# SCH_HackerCard_2024-08-30.net
KiCad netlist of a schematic drawn in EasyEDA
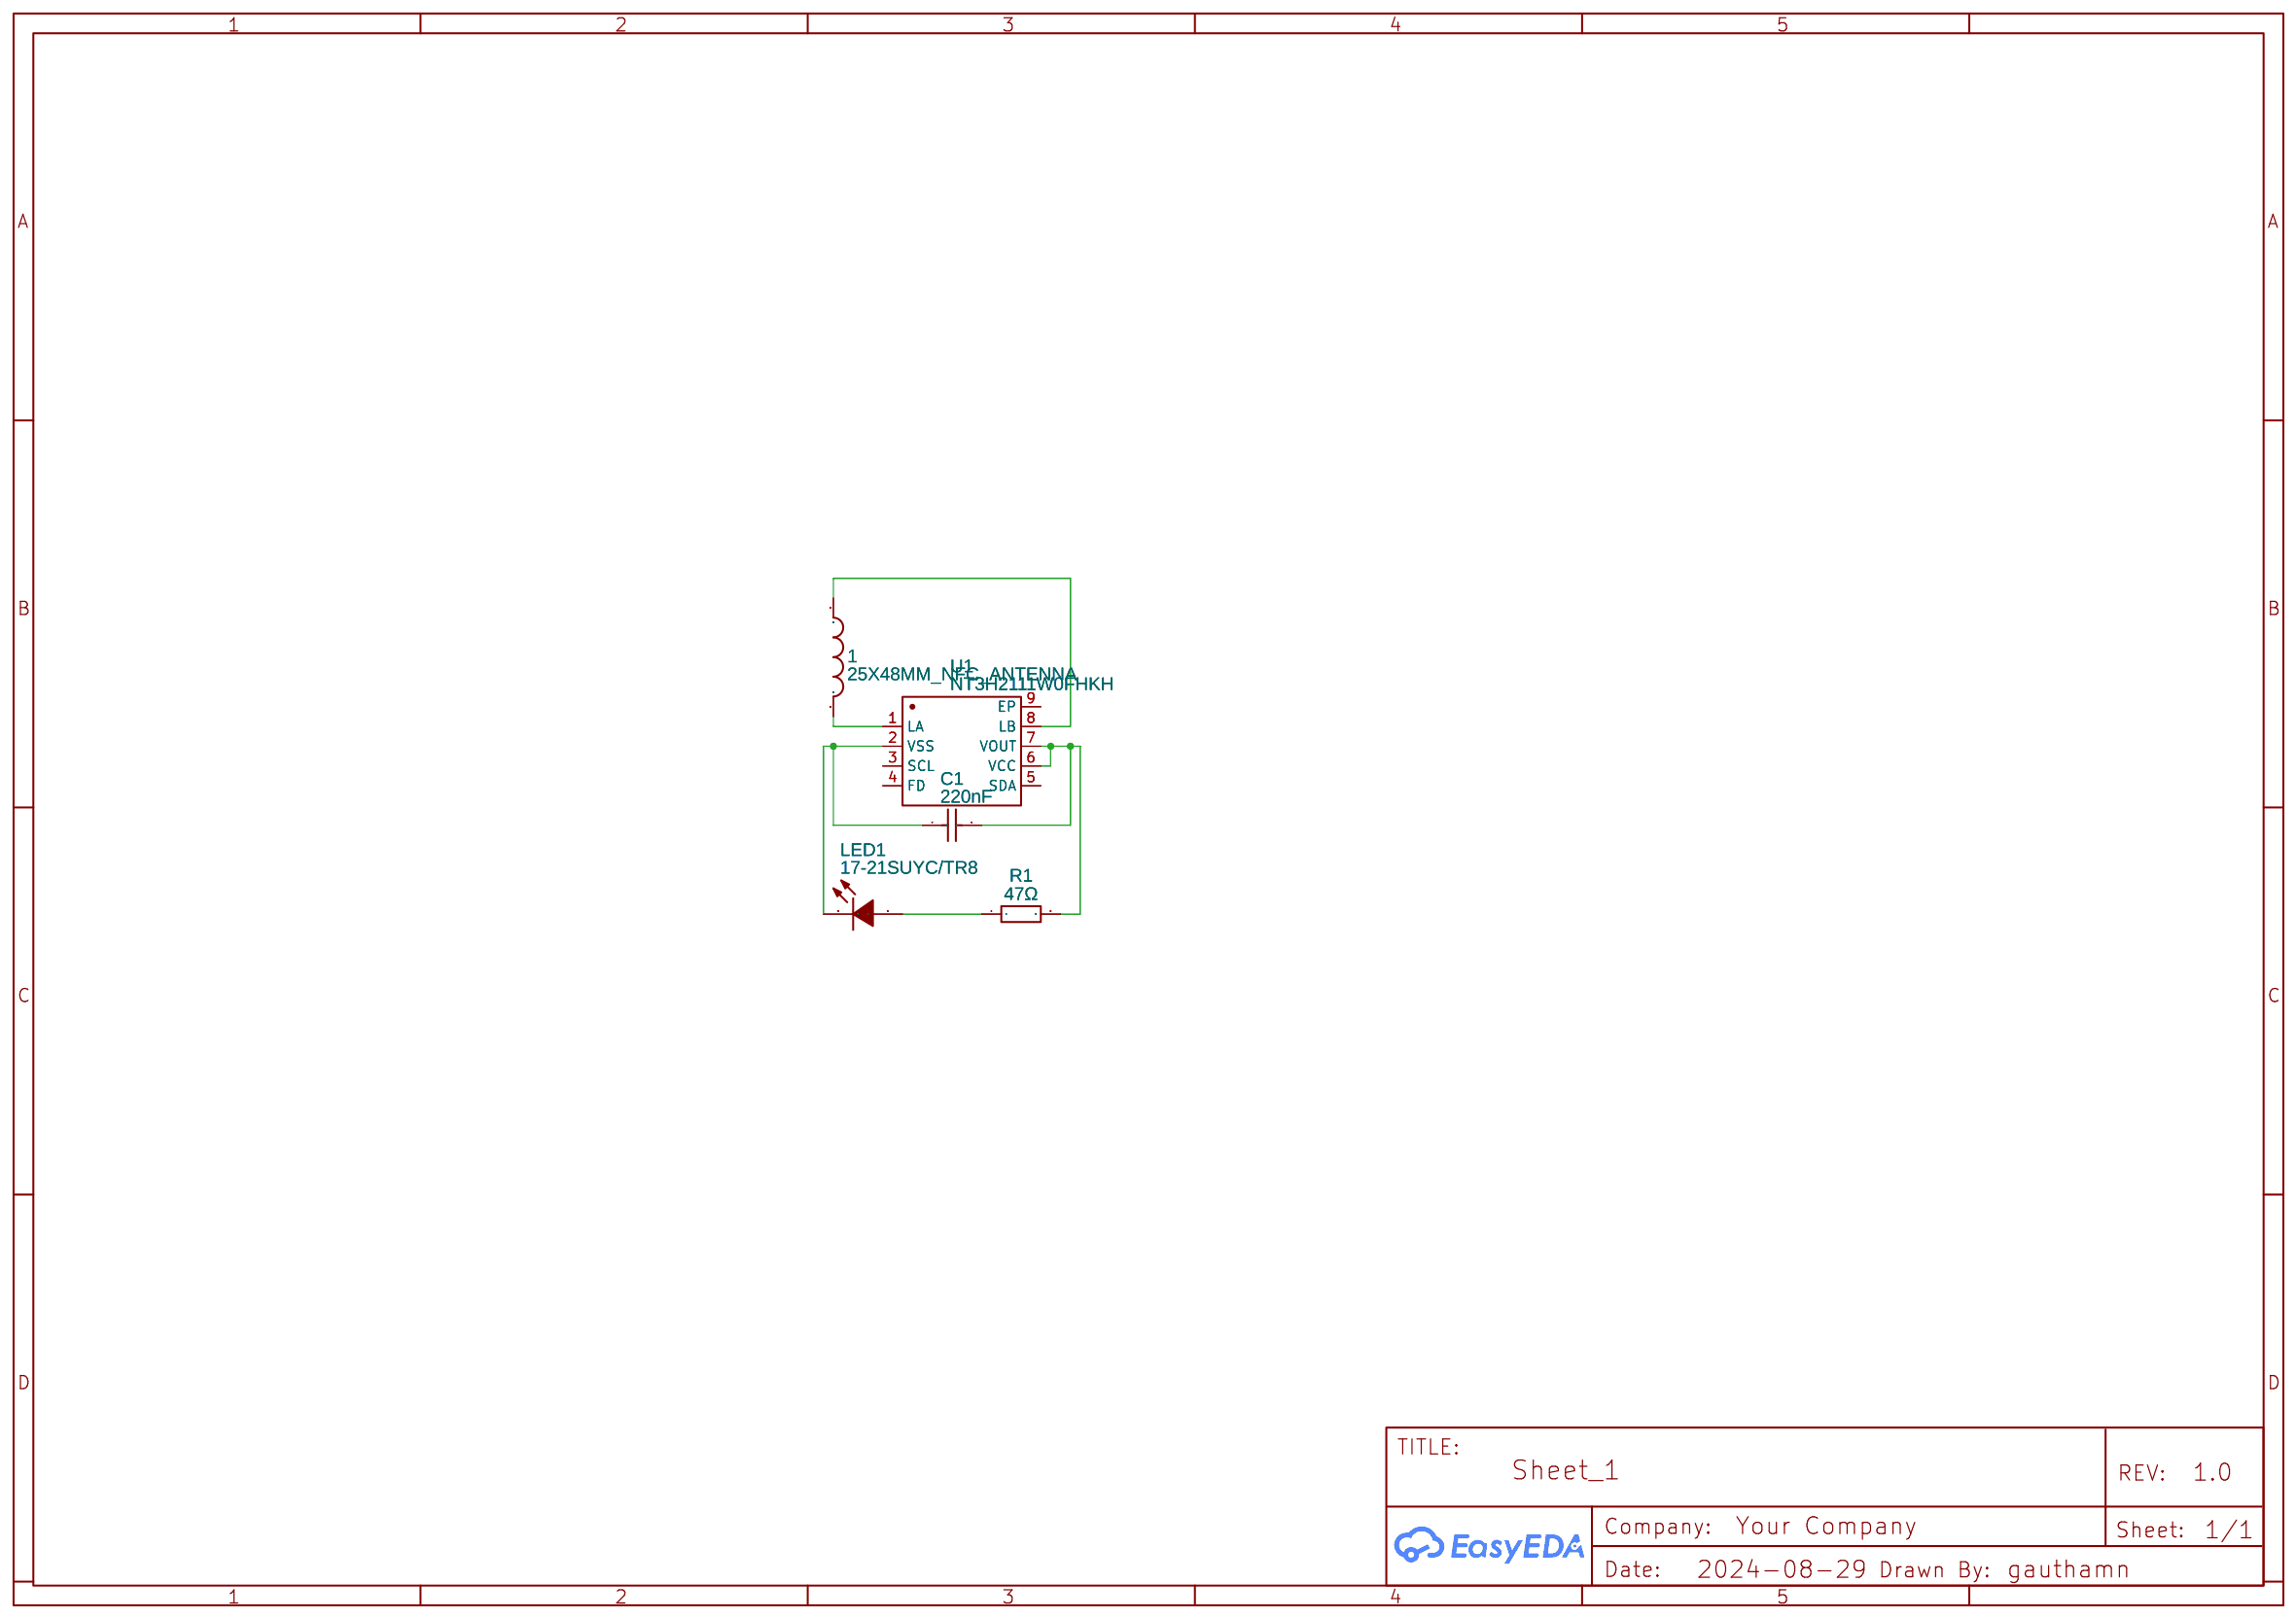
[diagram p0: schematic sheet]

(export (version "E")
  (design (tool "Eeschema 10.0.6"))
  (components
    (comp (ref "1") (value "25X48MM_NFC_ANTENNA") (libsource (lib "") (part "25X48MM_NFC_ANTENNA")))
    (comp (ref "C1")
      (value "220nF")
      (fields
        (field (name "Manufacturer Part") "CL10B224KA8NNNC")
        (field (name "Manufacturer") "SAMSUNG(三星)")
      )
      (libsource (lib "") (part "CL10B224KA8NNNC"))
    )
    (comp (ref "LED1")
      (value "17-21SUYC/TR8")
      (fields (field (name "Manufacturer Part") "KT-0805黄灯") (field (name "Manufacturer") "KENTO"))
      (libsource (lib "") (part "17-21SUYC/TR8"))
    )
    (comp (ref "R1")
      (value "47Ω")
      (fields
        (field (name "Manufacturer Part") "0603WAF470JT5E")
        (field (name "Manufacturer") "UNI-ROYAL(厚声)")
      )
      (libsource (lib "") (part "0603WAF470JT5E"))
    )
    (comp (ref "U1")
      (value "NT3H2111W0FHKH")
      (fields (field (name "Manufacturer") "NXP(恩智浦)"))
      (libsource (lib "") (part "NT3H2111W0FHKH"))
    )
  )
  (nets
    (net (code "1") (name "Net-(LED1-+)") (class "Default")
      (node (ref "LED1") (pin "1") (pinfunction "+_1") (pintype "unspecified"))
      (node (ref "R1") (pin "1") (pinfunction "1_1") (pintype "input"))
    )
    (net (code "2") (name "Net-(LED1--)") (class "Default")
      (node (ref "C1") (pin "1") (pinfunction "1_1") (pintype "input"))
      (node (ref "LED1") (pin "2") (pinfunction "-_2") (pintype "unspecified"))
      (node (ref "U1") (pin "2") (pinfunction "VSS_2") (pintype "unspecified"))
    )
    (net (code "3") (name "Net-(U1-LA)") (class "Default")
      (node (ref "1") (pin "P$2") (pinfunction "P$2_P$2") (pintype "bidirectional"))
      (node (ref "U1") (pin "1") (pinfunction "LA_1") (pintype "unspecified"))
    )
    (net (code "4") (name "Net-(U1-LB)") (class "Default")
      (node (ref "1") (pin "P$1") (pinfunction "P$1_P$1") (pintype "bidirectional"))
      (node (ref "U1") (pin "8") (pinfunction "LB_8") (pintype "unspecified"))
    )
    (net (code "5") (name "Net-(U1-VCC)") (class "Default")
      (node (ref "C1") (pin "2") (pinfunction "2_2") (pintype "input"))
      (node (ref "R1") (pin "2") (pinfunction "2_2") (pintype "input"))
      (node (ref "U1") (pin "6") (pinfunction "VCC_6") (pintype "unspecified"))
      (node (ref "U1") (pin "7") (pinfunction "VOUT_7") (pintype "unspecified"))
    )
    (net (code "6") (name "unconnected-(U1-EP-Pad9)") (class "Default")
      (node (ref "U1") (pin "9") (pinfunction "EP_9") (pintype "unspecified"))
    )
    (net (code "7") (name "unconnected-(U1-FD-Pad4)") (class "Default")
      (node (ref "U1") (pin "4") (pinfunction "FD_4") (pintype "unspecified"))
    )
    (net (code "8") (name "unconnected-(U1-SCL-Pad3)") (class "Default")
      (node (ref "U1") (pin "3") (pinfunction "SCL_3") (pintype "unspecified"))
    )
    (net (code "9") (name "unconnected-(U1-SDA-Pad5)") (class "Default")
      (node (ref "U1") (pin "5") (pinfunction "SDA_5") (pintype "unspecified"))
    )
  )
)
